# MainBoard.net
KiCad netlist of a schematic drawn in EAGLE
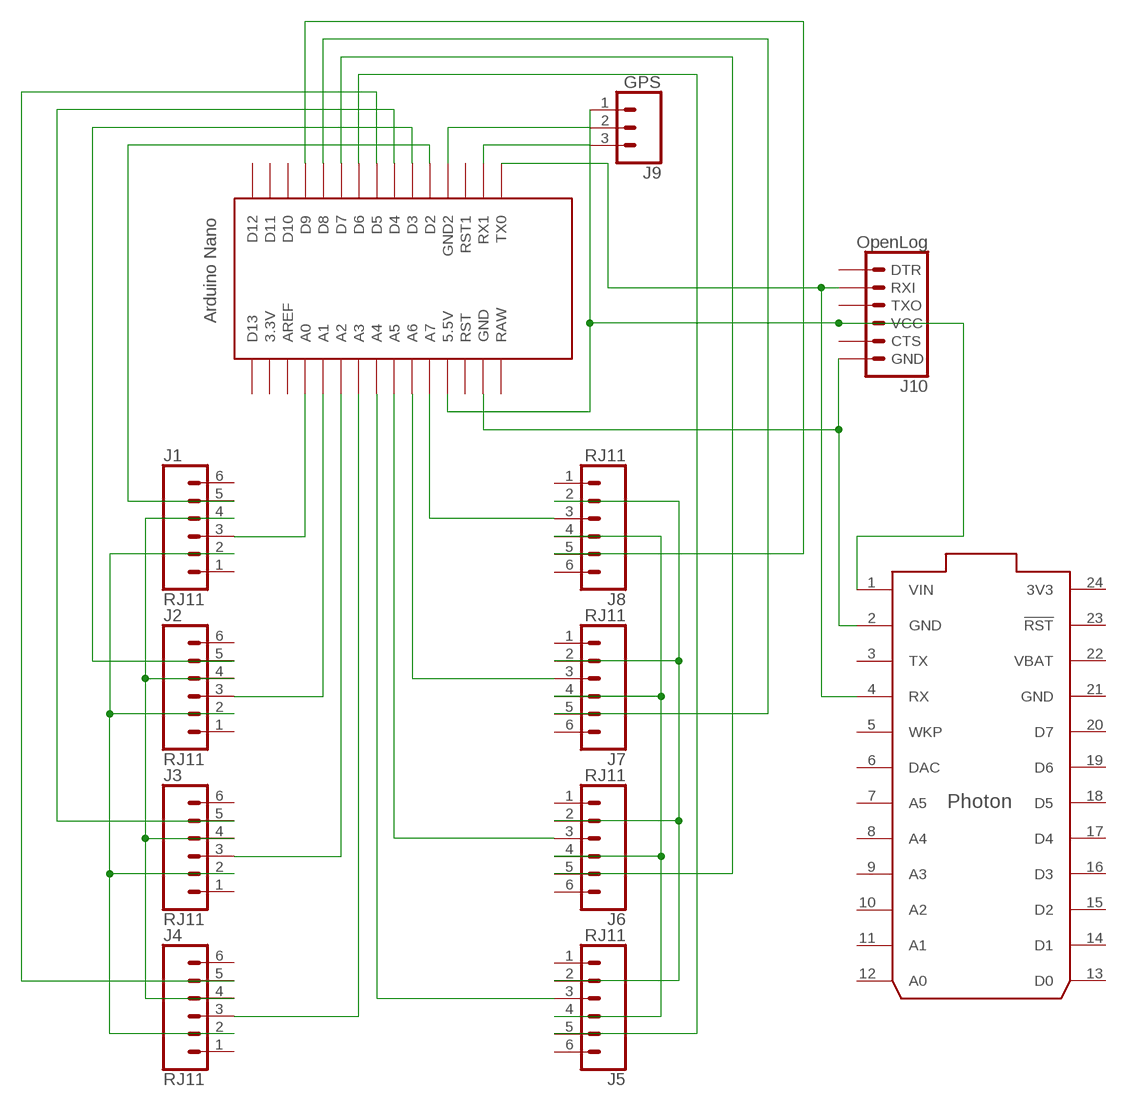
[diagram p0: schematic, sheet 1]

(export (version "E")
  (design (tool "Eeschema 10.0.6"))
  (components
    (comp (ref "J1")
      (value "RJ11")
      (footprint "eagle-import:RJ11-6")
      (libsource (lib "eagle-import") (part "RJ11-6"))
    )
    (comp (ref "J2")
      (value "RJ11")
      (footprint "eagle-import:RJ11-6")
      (libsource (lib "eagle-import") (part "RJ11-6"))
    )
    (comp (ref "J3")
      (value "RJ11")
      (footprint "eagle-import:RJ11-6")
      (libsource (lib "eagle-import") (part "RJ11-6"))
    )
    (comp (ref "J4")
      (value "RJ11")
      (footprint "eagle-import:RJ11-6")
      (libsource (lib "eagle-import") (part "RJ11-6"))
    )
    (comp (ref "J5")
      (value "RJ11")
      (footprint "eagle-import:RJ11-6")
      (libsource (lib "eagle-import") (part "RJ11-6"))
    )
    (comp (ref "J6")
      (value "RJ11")
      (footprint "eagle-import:RJ11-6")
      (libsource (lib "eagle-import") (part "RJ11-6"))
    )
    (comp (ref "J7")
      (value "RJ11")
      (footprint "eagle-import:RJ11-6")
      (libsource (lib "eagle-import") (part "RJ11-6"))
    )
    (comp (ref "J8")
      (value "RJ11")
      (footprint "eagle-import:RJ11-6")
      (libsource (lib "eagle-import") (part "RJ11-6"))
    )
    (comp (ref "J9")
      (value "GPS")
      (footprint "eagle-import:1X03")
      (libsource (lib "eagle-import") (part "CONN_03"))
    )
    (comp (ref "J10")
      (value "OpenLog")
      (footprint "eagle-import:1X06")
      (libsource (lib "eagle-import") (part "6_PIN_SERIAL_TARGET"))
    )
    (comp (ref "U$1")
      (value "NANO")
      (footprint "eagle-import:NANO")
      (libsource (lib "eagle-import") (part "NANO"))
    )
    (comp (ref "U$2")
      (value "PHOTON_WITH_HEADERS")
      (footprint "eagle-import:PHOTON")
      (libsource (lib "eagle-import") (part "PHOTON_WITH_HEADERS"))
    )
  )
  (nets
    (net (code "1") (name "/3V3") (class "Default")
      (node (ref "U$2") (pin "24") (pinfunction "3V3_24") (pintype "power_in"))
    )
    (net (code "2") (name "/GND") (class "Default")
      (node (ref "U$2") (pin "21") (pinfunction "GND_21") (pintype "power_in"))
    )
    (net (code "3") (name "/VBAT") (class "Default")
      (node (ref "U$2") (pin "22") (pinfunction "VBAT_22") (pintype "power_in"))
    )
    (net (code "4") (name "Net-(J1-Pad2)") (class "Default")
      (node (ref "J1") (pin "2") (pinfunction "2_2") (pintype "passive"))
      (node (ref "J2") (pin "2") (pinfunction "2_2") (pintype "passive"))
      (node (ref "J3") (pin "2") (pinfunction "2_2") (pintype "passive"))
      (node (ref "J4") (pin "2") (pinfunction "2_2") (pintype "passive"))
    )
    (net (code "5") (name "Net-(J1-Pad3)") (class "Default")
      (node (ref "J1") (pin "3") (pinfunction "3_3") (pintype "passive"))
      (node (ref "U$1") (pin "A0") (pinfunction "A0_A0") (pintype "bidirectional"))
    )
    (net (code "6") (name "Net-(J1-Pad4)") (class "Default")
      (node (ref "J1") (pin "4") (pinfunction "4_4") (pintype "passive"))
      (node (ref "J2") (pin "4") (pinfunction "4_4") (pintype "passive"))
      (node (ref "J3") (pin "4") (pinfunction "4_4") (pintype "passive"))
      (node (ref "J4") (pin "4") (pinfunction "4_4") (pintype "passive"))
    )
    (net (code "7") (name "Net-(J1-Pad5)") (class "Default")
      (node (ref "J1") (pin "5") (pinfunction "5_5") (pintype "passive"))
      (node (ref "U$1") (pin "D2") (pinfunction "D2_D2") (pintype "bidirectional"))
    )
    (net (code "8") (name "Net-(J2-Pad3)") (class "Default")
      (node (ref "J2") (pin "3") (pinfunction "3_3") (pintype "passive"))
      (node (ref "U$1") (pin "A1") (pinfunction "A1_A1") (pintype "bidirectional"))
    )
    (net (code "9") (name "Net-(J2-Pad5)") (class "Default")
      (node (ref "J2") (pin "5") (pinfunction "5_5") (pintype "passive"))
      (node (ref "U$1") (pin "D3") (pinfunction "D3_D3") (pintype "bidirectional"))
    )
    (net (code "10") (name "Net-(J3-Pad3)") (class "Default")
      (node (ref "J3") (pin "3") (pinfunction "3_3") (pintype "passive"))
      (node (ref "U$1") (pin "A2") (pinfunction "A2_A2") (pintype "bidirectional"))
    )
    (net (code "11") (name "Net-(J3-Pad5)") (class "Default")
      (node (ref "J3") (pin "5") (pinfunction "5_5") (pintype "passive"))
      (node (ref "U$1") (pin "D4") (pinfunction "D4_D4") (pintype "bidirectional"))
    )
    (net (code "12") (name "Net-(J4-Pad3)") (class "Default")
      (node (ref "J4") (pin "3") (pinfunction "3_3") (pintype "passive"))
      (node (ref "U$1") (pin "A3") (pinfunction "A3_A3") (pintype "bidirectional"))
    )
    (net (code "13") (name "Net-(J4-Pad5)") (class "Default")
      (node (ref "J4") (pin "5") (pinfunction "5_5") (pintype "passive"))
      (node (ref "U$1") (pin "D5") (pinfunction "D5_D5") (pintype "bidirectional"))
    )
    (net (code "14") (name "Net-(J5-Pad2)") (class "Default")
      (node (ref "J5") (pin "2") (pinfunction "2_2") (pintype "passive"))
      (node (ref "J6") (pin "2") (pinfunction "2_2") (pintype "passive"))
      (node (ref "J7") (pin "2") (pinfunction "2_2") (pintype "passive"))
      (node (ref "J8") (pin "2") (pinfunction "2_2") (pintype "passive"))
    )
    (net (code "15") (name "Net-(J5-Pad3)") (class "Default")
      (node (ref "J5") (pin "3") (pinfunction "3_3") (pintype "passive"))
      (node (ref "U$1") (pin "A4") (pinfunction "A4_A4") (pintype "bidirectional"))
    )
    (net (code "16") (name "Net-(J5-Pad4)") (class "Default")
      (node (ref "J5") (pin "4") (pinfunction "4_4") (pintype "passive"))
      (node (ref "J6") (pin "4") (pinfunction "4_4") (pintype "passive"))
      (node (ref "J7") (pin "4") (pinfunction "4_4") (pintype "passive"))
      (node (ref "J8") (pin "4") (pinfunction "4_4") (pintype "passive"))
    )
    (net (code "17") (name "Net-(J5-Pad5)") (class "Default")
      (node (ref "J5") (pin "5") (pinfunction "5_5") (pintype "passive"))
      (node (ref "U$1") (pin "D6") (pinfunction "D6_D6") (pintype "bidirectional"))
    )
    (net (code "18") (name "Net-(J6-Pad3)") (class "Default")
      (node (ref "J6") (pin "3") (pinfunction "3_3") (pintype "passive"))
      (node (ref "U$1") (pin "A5") (pinfunction "A5_A5") (pintype "bidirectional"))
    )
    (net (code "19") (name "Net-(J6-Pad5)") (class "Default")
      (node (ref "J6") (pin "5") (pinfunction "5_5") (pintype "passive"))
      (node (ref "U$1") (pin "D7") (pinfunction "D7_D7") (pintype "bidirectional"))
    )
    (net (code "20") (name "Net-(J7-Pad3)") (class "Default")
      (node (ref "J7") (pin "3") (pinfunction "3_3") (pintype "passive"))
      (node (ref "U$1") (pin "A6") (pinfunction "A6_A6") (pintype "bidirectional"))
    )
    (net (code "21") (name "Net-(J7-Pad5)") (class "Default")
      (node (ref "J7") (pin "5") (pinfunction "5_5") (pintype "passive"))
      (node (ref "U$1") (pin "D8") (pinfunction "D8_D8") (pintype "bidirectional"))
    )
    (net (code "22") (name "Net-(J8-Pad3)") (class "Default")
      (node (ref "J8") (pin "3") (pinfunction "3_3") (pintype "passive"))
      (node (ref "U$1") (pin "A7") (pinfunction "A7_A7") (pintype "bidirectional"))
    )
    (net (code "23") (name "Net-(J8-Pad5)") (class "Default")
      (node (ref "J8") (pin "5") (pinfunction "5_5") (pintype "passive"))
      (node (ref "U$1") (pin "D9") (pinfunction "D9_D9") (pintype "bidirectional"))
    )
    (net (code "24") (name "Net-(J9-Pad3)") (class "Default")
      (node (ref "J9") (pin "3") (pinfunction "3_3") (pintype "passive"))
      (node (ref "U$1") (pin "RX1") (pinfunction "RX1_RX1") (pintype "bidirectional"))
    )
    (net (code "25") (name "Net-(J10-GND)") (class "Default")
      (node (ref "J10") (pin "6") (pinfunction "GND_6") (pintype "passive"))
      (node (ref "U$1") (pin "GND") (pinfunction "GND_GND") (pintype "bidirectional"))
      (node (ref "U$2") (pin "2") (pinfunction "GND_2") (pintype "power_in"))
    )
    (net (code "26") (name "Net-(J10-RXI)") (class "Default")
      (node (ref "J10") (pin "2") (pinfunction "RXI_2") (pintype "passive"))
      (node (ref "U$1") (pin "TX0") (pinfunction "TX0_TX0") (pintype "bidirectional"))
      (node (ref "U$2") (pin "4") (pinfunction "RX_4") (pintype "bidirectional"))
    )
    (net (code "27") (name "Net-(J10-VCC)") (class "Default")
      (node (ref "J10") (pin "4") (pinfunction "VCC_4") (pintype "passive"))
      (node (ref "J9") (pin "1") (pinfunction "1_1") (pintype "passive"))
      (node (ref "U$1") (pin "5V") (pinfunction "5.5V_5V") (pintype "bidirectional"))
      (node (ref "U$2") (pin "1") (pinfunction "VIN_1") (pintype "power_in"))
    )
    (net (code "28") (name "Net-(U$1-GND2)") (class "Default")
      (node (ref "J9") (pin "2") (pinfunction "2_2") (pintype "passive"))
      (node (ref "U$1") (pin "GND1") (pinfunction "GND2_GND1") (pintype "bidirectional"))
    )
    (net (code "29") (name "unconnected-(J1-Pad1)") (class "Default")
      (node (ref "J1") (pin "1") (pinfunction "1_1") (pintype "passive"))
    )
    (net (code "30") (name "unconnected-(J1-Pad6)") (class "Default")
      (node (ref "J1") (pin "6") (pinfunction "6_6") (pintype "passive"))
    )
    (net (code "31") (name "unconnected-(J2-Pad1)") (class "Default")
      (node (ref "J2") (pin "1") (pinfunction "1_1") (pintype "passive"))
    )
    (net (code "32") (name "unconnected-(J2-Pad6)") (class "Default")
      (node (ref "J2") (pin "6") (pinfunction "6_6") (pintype "passive"))
    )
    (net (code "33") (name "unconnected-(J3-Pad1)") (class "Default")
      (node (ref "J3") (pin "1") (pinfunction "1_1") (pintype "passive"))
    )
    (net (code "34") (name "unconnected-(J3-Pad6)") (class "Default")
      (node (ref "J3") (pin "6") (pinfunction "6_6") (pintype "passive"))
    )
    (net (code "35") (name "unconnected-(J4-Pad1)") (class "Default")
      (node (ref "J4") (pin "1") (pinfunction "1_1") (pintype "passive"))
    )
    (net (code "36") (name "unconnected-(J4-Pad6)") (class "Default")
      (node (ref "J4") (pin "6") (pinfunction "6_6") (pintype "passive"))
    )
    (net (code "37") (name "unconnected-(J5-Pad1)") (class "Default")
      (node (ref "J5") (pin "1") (pinfunction "1_1") (pintype "passive"))
    )
    (net (code "38") (name "unconnected-(J5-Pad6)") (class "Default")
      (node (ref "J5") (pin "6") (pinfunction "6_6") (pintype "passive"))
    )
    (net (code "39") (name "unconnected-(J6-Pad1)") (class "Default")
      (node (ref "J6") (pin "1") (pinfunction "1_1") (pintype "passive"))
    )
    (net (code "40") (name "unconnected-(J6-Pad6)") (class "Default")
      (node (ref "J6") (pin "6") (pinfunction "6_6") (pintype "passive"))
    )
    (net (code "41") (name "unconnected-(J7-Pad1)") (class "Default")
      (node (ref "J7") (pin "1") (pinfunction "1_1") (pintype "passive"))
    )
    (net (code "42") (name "unconnected-(J7-Pad6)") (class "Default")
      (node (ref "J7") (pin "6") (pinfunction "6_6") (pintype "passive"))
    )
    (net (code "43") (name "unconnected-(J8-Pad1)") (class "Default")
      (node (ref "J8") (pin "1") (pinfunction "1_1") (pintype "passive"))
    )
    (net (code "44") (name "unconnected-(J8-Pad6)") (class "Default")
      (node (ref "J8") (pin "6") (pinfunction "6_6") (pintype "passive"))
    )
    (net (code "45") (name "unconnected-(J10-CTS-Pad5)") (class "Default")
      (node (ref "J10") (pin "5") (pinfunction "CTS_5") (pintype "passive"))
    )
    (net (code "46") (name "unconnected-(J10-DTR-Pad1)") (class "Default")
      (node (ref "J10") (pin "1") (pinfunction "DTR_1") (pintype "passive"))
    )
    (net (code "47") (name "unconnected-(J10-TXO-Pad3)") (class "Default")
      (node (ref "J10") (pin "3") (pinfunction "TXO_3") (pintype "passive"))
    )
    (net (code "48") (name "unconnected-(U$1-Pad3.3V)") (class "Default")
      (node (ref "U$1") (pin "3.3V") (pinfunction "3.3V_3.3V") (pintype "bidirectional"))
    )
    (net (code "49") (name "unconnected-(U$1-PadAREF)") (class "Default")
      (node (ref "U$1") (pin "AREF") (pinfunction "AREF_AREF") (pintype "bidirectional"))
    )
    (net (code "50") (name "unconnected-(U$1-PadD10)") (class "Default")
      (node (ref "U$1") (pin "D10") (pinfunction "D10_D10") (pintype "bidirectional"))
    )
    (net (code "51") (name "unconnected-(U$1-PadD11)") (class "Default")
      (node (ref "U$1") (pin "D11") (pinfunction "D11_D11") (pintype "bidirectional"))
    )
    (net (code "52") (name "unconnected-(U$1-PadD12)") (class "Default")
      (node (ref "U$1") (pin "D12") (pinfunction "D12_D12") (pintype "bidirectional"))
    )
    (net (code "53") (name "unconnected-(U$1-PadD13)") (class "Default")
      (node (ref "U$1") (pin "D13") (pinfunction "D13_D13") (pintype "bidirectional"))
    )
    (net (code "54") (name "unconnected-(U$1-PadICSP1)") (class "Default")
      (node (ref "U$1") (pin "ICSP1") (pinfunction "ICSP1_ICSP1") (pintype "bidirectional"))
    )
    (net (code "55") (name "unconnected-(U$1-PadICSP2)") (class "Default")
      (node (ref "U$1") (pin "ICSP2") (pinfunction "ICSP2_ICSP2") (pintype "bidirectional"))
    )
    (net (code "56") (name "unconnected-(U$1-PadICSP3)") (class "Default")
      (node (ref "U$1") (pin "ICSP3") (pinfunction "ICSP3_ICSP3") (pintype "bidirectional"))
    )
    (net (code "57") (name "unconnected-(U$1-PadICSP4)") (class "Default")
      (node (ref "U$1") (pin "ICSP4") (pinfunction "ICSP4_ICSP4") (pintype "bidirectional"))
    )
    (net (code "58") (name "unconnected-(U$1-PadICSP5)") (class "Default")
      (node (ref "U$1") (pin "ICSP5") (pinfunction "ICSP5_ICSP5") (pintype "bidirectional"))
    )
    (net (code "59") (name "unconnected-(U$1-PadICSP6)") (class "Default")
      (node (ref "U$1") (pin "ICSP6") (pinfunction "ICSP6_ICSP6") (pintype "bidirectional"))
    )
    (net (code "60") (name "unconnected-(U$1-PadRAW)") (class "Default")
      (node (ref "U$1") (pin "RAW") (pinfunction "RAW_RAW") (pintype "bidirectional"))
    )
    (net (code "61") (name "unconnected-(U$1-PadRST)") (class "Default")
      (node (ref "U$1") (pin "RST") (pinfunction "RST_RST") (pintype "bidirectional"))
    )
    (net (code "62") (name "unconnected-(U$1-PadRST1)") (class "Default")
      (node (ref "U$1") (pin "RST1") (pinfunction "RST1_RST1") (pintype "bidirectional"))
    )
    (net (code "63") (name "unconnected-(U$2-A0-Pad12)") (class "Default")
      (node (ref "U$2") (pin "12") (pinfunction "A0_12") (pintype "bidirectional"))
    )
    (net (code "64") (name "unconnected-(U$2-A1-Pad11)") (class "Default")
      (node (ref "U$2") (pin "11") (pinfunction "A1_11") (pintype "bidirectional"))
    )
    (net (code "65") (name "unconnected-(U$2-A2-Pad10)") (class "Default")
      (node (ref "U$2") (pin "10") (pinfunction "A2_10") (pintype "bidirectional"))
    )
    (net (code "66") (name "unconnected-(U$2-A3-Pad9)") (class "Default")
      (node (ref "U$2") (pin "9") (pinfunction "A3_9") (pintype "bidirectional"))
    )
    (net (code "67") (name "unconnected-(U$2-A4-Pad8)") (class "Default")
      (node (ref "U$2") (pin "8") (pinfunction "A4_8") (pintype "bidirectional"))
    )
    (net (code "68") (name "unconnected-(U$2-A5-Pad7)") (class "Default")
      (node (ref "U$2") (pin "7") (pinfunction "A5_7") (pintype "bidirectional"))
    )
    (net (code "69") (name "unconnected-(U$2-D0-Pad13)") (class "Default")
      (node (ref "U$2") (pin "13") (pinfunction "D0_13") (pintype "bidirectional"))
    )
    (net (code "70") (name "unconnected-(U$2-D1-Pad14)") (class "Default")
      (node (ref "U$2") (pin "14") (pinfunction "D1_14") (pintype "bidirectional"))
    )
    (net (code "71") (name "unconnected-(U$2-D2-Pad15)") (class "Default")
      (node (ref "U$2") (pin "15") (pinfunction "D2_15") (pintype "bidirectional"))
    )
    (net (code "72") (name "unconnected-(U$2-D3-Pad16)") (class "Default")
      (node (ref "U$2") (pin "16") (pinfunction "D3_16") (pintype "bidirectional"))
    )
    (net (code "73") (name "unconnected-(U$2-D4-Pad17)") (class "Default")
      (node (ref "U$2") (pin "17") (pinfunction "D4_17") (pintype "bidirectional"))
    )
    (net (code "74") (name "unconnected-(U$2-D5-Pad18)") (class "Default")
      (node (ref "U$2") (pin "18") (pinfunction "D5_18") (pintype "bidirectional"))
    )
    (net (code "75") (name "unconnected-(U$2-D6-Pad19)") (class "Default")
      (node (ref "U$2") (pin "19") (pinfunction "D6_19") (pintype "bidirectional"))
    )
    (net (code "76") (name "unconnected-(U$2-D7-Pad20)") (class "Default")
      (node (ref "U$2") (pin "20") (pinfunction "D7_20") (pintype "bidirectional"))
    )
    (net (code "77") (name "unconnected-(U$2-DAC-Pad6)") (class "Default")
      (node (ref "U$2") (pin "6") (pinfunction "DAC_6") (pintype "bidirectional"))
    )
    (net (code "78") (name "unconnected-(U$2-TX-Pad3)") (class "Default")
      (node (ref "U$2") (pin "3") (pinfunction "TX_3") (pintype "bidirectional"))
    )
    (net (code "79") (name "unconnected-(U$2-WKP-Pad5)") (class "Default")
      (node (ref "U$2") (pin "5") (pinfunction "WKP_5") (pintype "bidirectional"))
    )
    (net (code "80") (name "unconnected-(U$2-~{RST}-Pad23)") (class "Default")
      (node (ref "U$2") (pin "23") (pinfunction "~{RST}_23") (pintype "bidirectional"))
    )
  )
)
